# Power_Supply.net
KiCad netlist of a schematic drawn in Altium Designer
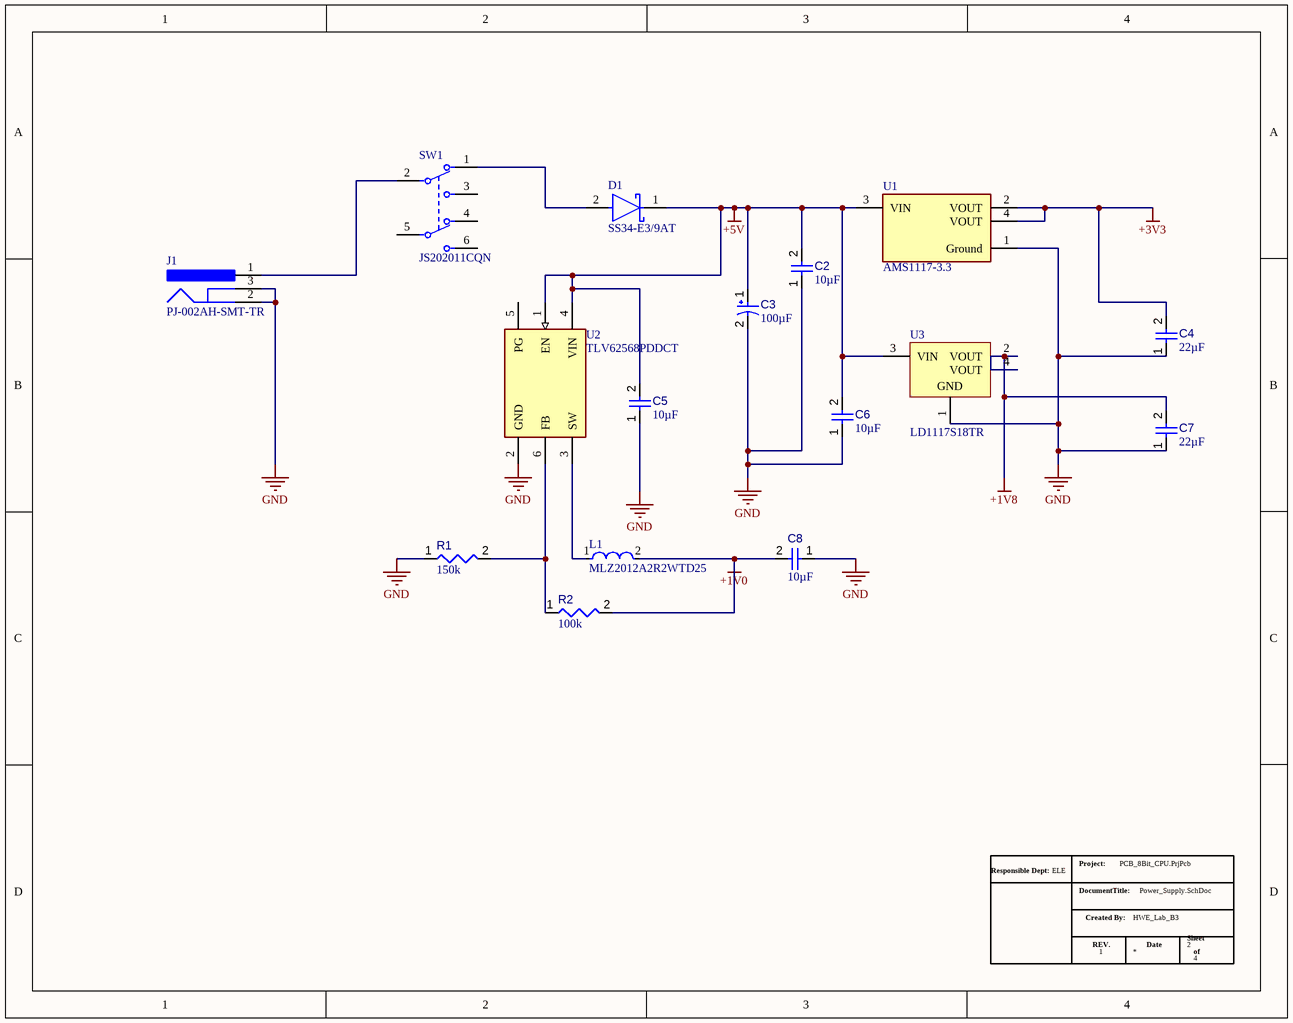
[diagram p0: Power_Supply.SchDoc]

(export (version "E")
  (design (tool "Eeschema 10.0.6"))
  (components
    (comp (ref "C2")
      (value "10µF")
      (footprint "CAPC0805(2012)145_L")
      (description "Chip Capacitor, 10µF +/-20%, 25V, 0805, Thickness 1.45 mm")
      (fields (field (name "TOLERANCE") "10%") (field (name "Comment") "Capacitor 10µF +/-20% 25V 0805"))
      (libsource (lib "MD RUHUL KUDDUS SALEH") (part "CAP-NP-2"))
    )
    (comp (ref "C3")
      (value "100µF")
      (footprint "PNSC-6TPE150MAZB_L")
      (fields (field (name "TOLERANCE") "20%") (field (name "Comment") "Capacitor 6.8µF +/-20% 35V B2"))
      (libsource (lib "MD RUHUL KUDDUS SALEH") (part "CAP-P-2"))
    )
    (comp (ref "C4")
      (value "22µF")
      (footprint "CAPC0805(2012)145_L")
      (description "Chip Capacitor, 10µF +/-20%, 25V, 0805, Thickness 1.45 mm")
      (fields (field (name "TOLERANCE") "10%") (field (name "Comment") "Capacitor 10µF +/-20% 25V 0805"))
      (libsource (lib "MD RUHUL KUDDUS SALEH") (part "CAP-NP-2"))
    )
    (comp (ref "C5")
      (value "10µF")
      (footprint "CAPC0805(2012)145_L")
      (description "Chip Capacitor, 10µF +/-20%, 25V, 0805, Thickness 1.45 mm")
      (fields (field (name "TOLERANCE") "10%") (field (name "Comment") "Capacitor 10µF +/-20% 25V 0805"))
      (libsource (lib "MD RUHUL KUDDUS SALEH") (part "CAP-NP-2"))
    )
    (comp (ref "C6")
      (value "10µF")
      (footprint "CAPC0805(2012)145_L")
      (description "Chip Capacitor, 10µF +/-20%, 25V, 0805, Thickness 1.45 mm")
      (fields (field (name "TOLERANCE") "10%") (field (name "Comment") "Capacitor 10µF +/-20% 25V 0805"))
      (libsource (lib "MD RUHUL KUDDUS SALEH") (part "CAP-NP-2"))
    )
    (comp (ref "C7")
      (value "22µF")
      (footprint "CAPC0805(2012)145_L")
      (description "Chip Capacitor, 10µF +/-20%, 25V, 0805, Thickness 1.45 mm")
      (fields (field (name "TOLERANCE") "10%") (field (name "Comment") "Capacitor 10µF +/-20% 25V 0805"))
      (libsource (lib "MD RUHUL KUDDUS SALEH") (part "CAP-NP-2"))
    )
    (comp (ref "C8")
      (value "10µF")
      (footprint "CAPC0805(2012)145_L")
      (description "Chip Capacitor, 10µF +/-20%, 25V, 0805, Thickness 1.45 mm")
      (fields (field (name "TOLERANCE") "10%") (field (name "Comment") "Capacitor 10µF +/-20% 25V 0805"))
      (libsource (lib "MD RUHUL KUDDUS SALEH") (part "CAP-NP-2"))
    )
    (comp (ref "D1")
      (value "SS34-E3/9AT")
      (footprint "FP-SMC-MFG")
      (description "DIODE SCHOTTKY 40V 3A DO214AB")
      (libsource (lib "Altium Content Vault") (part "c1678fac7984e62e0809fbf79c06691"))
    )
    (comp (ref "J1")
      (value "PJ-002AH-SMT-TR")
      (footprint "CUI-PJ-002AH-4_V")
      (description "DC Power Jack, Right Angle, -25 to 85 degC, 4-Pin 14.8 x 9 x 11 mm SMD, RoHS, Tape and Reel")
      (fields (field (name "MANUFACTURER") "CUIInc.") (field (name "PARTNUMBER") "PJ-002AH"))
      (libsource (lib "Altium Content Vault") (part "JACK-2CD3-RN_B"))
    )
    (comp (ref "L1")
      (value "MLZ2012A2R2WTD25")
      (footprint "FP-MLZ2012-0_85-MFG")
      (description "Shielded Multilayer Inductor 2.2uH ±20% 650mA 195mΩ AEC-Q200 SMD 0805")
      (fields (field (name "TOLERANCE") "20%"))
      (libsource (lib "Altium Content Vault") (part "725321dda6339637d4d059423bc1c3c"))
    )
    (comp (ref "R1")
      (value "150k")
      (footprint "RESC0402(1005)_L")
      (description "Chip Resistor, 100 kOhms, +/-1 %, 63 mW, -55 to 155 degC, 0402")
      (fields (field (name "TOLERANCE") "1%") (field (name "POWER") "63mW"))
      (libsource (lib "MD RUHUL KUDDUS SALEH") (part "RES-2"))
    )
    (comp (ref "R2")
      (value "100k")
      (footprint "RESC0402(1005)_L")
      (description "Chip Resistor, 100 kOhms, +/-1 %, 63 mW, -55 to 155 degC, 0402")
      (fields (field (name "TOLERANCE") "1%") (field (name "POWER") "63mW"))
      (libsource (lib "MD RUHUL KUDDUS SALEH") (part "RES-2"))
    )
    (comp (ref "SW1")
      (value "JS202011CQN")
      (footprint "FP-JS202011CQN-MFG")
      (description "SWITCH SLIDE DPDT 300MA 6V")
      (libsource (lib "Altium Content Vault") (part "a9e2ad50e97b660f430b512a9354c8c"))
    )
    (comp (ref "U1")
      (value "AMS1117-3.3")
      (footprint "FP-AMS1117-IPC_C")
      (description "LDO Voltage Regulators 1A, 3.3V")
      (fields
        (field (name "OCTOPART") "https://octopart.com/ams1117-3.3-advanced+monolithic+systems-25899300")
        (field (name "MANUFACTURER") "Advanced Monolithic Systems")
      )
      (libsource (lib "Altium Content Vault") (part "8bdbb5f8e77002000e30dd2845d0354"))
    )
    (comp (ref "U2")
      (value "TLV62568PDDCT")
      (footprint "FP-DDC0006A-MFG")
      (description "IC REG BUCK ADJ 1A TSOT23-6")
      (libsource (lib "Altium Content Vault") (part "fcfae234c2e21ab116172289ae38564"))
    )
    (comp (ref "U3")
      (value "LD1117S18TR")
      (footprint "SOT-223_M")
      (description "Fixed Low Drop Positive Voltage Regulator, 1.8V, 4-Pin SOT-223, Tape and Reel")
      (libsource (lib "Altium Content Vault") (part "PM-REG-LD1117-SOT4"))
    )
  )
  (nets
    (net (code "1") (name "+1V0") (class "Default")
      (node (ref "C8") (pin "2") (pinfunction "2_2") (pintype "passive"))
      (node (ref "L1") (pin "2") (pinfunction "2_2") (pintype "passive"))
      (node (ref "R2") (pin "2") (pinfunction "2_2") (pintype "passive"))
    )
    (net (code "2") (name "+1V8") (class "Default")
      (node (ref "C7") (pin "2") (pinfunction "2_2") (pintype "passive"))
      (node (ref "U3") (pin "2") (pinfunction "VOUT_2") (pintype "power_in"))
      (node (ref "U3") (pin "4") (pinfunction "VOUT_4") (pintype "power_in"))
    )
    (net (code "3") (name "+3V3") (class "Default")
      (node (ref "C4") (pin "2") (pinfunction "2_2") (pintype "passive"))
      (node (ref "U1") (pin "2") (pinfunction "VOUT_2") (pintype "passive"))
      (node (ref "U1") (pin "4") (pinfunction "VOUT_4") (pintype "passive"))
    )
    (net (code "4") (name "+5V") (class "Default")
      (node (ref "C2") (pin "2") (pinfunction "2_2") (pintype "passive"))
      (node (ref "C3") (pin "1") (pinfunction "1_1") (pintype "passive"))
      (node (ref "C5") (pin "2") (pinfunction "2_2") (pintype "passive"))
      (node (ref "C6") (pin "2") (pinfunction "2_2") (pintype "passive"))
      (node (ref "D1") (pin "1") (pinfunction "C_1") (pintype "passive"))
      (node (ref "U1") (pin "3") (pinfunction "VIN_3") (pintype "power_in"))
      (node (ref "U2") (pin "1") (pinfunction "EN_1") (pintype "input"))
      (node (ref "U2") (pin "4") (pinfunction "VIN_4") (pintype "power_in"))
      (node (ref "U3") (pin "3") (pinfunction "VIN_3") (pintype "power_in"))
    )
    (net (code "5") (name "GND") (class "Default")
      (node (ref "C2") (pin "1") (pinfunction "1_1") (pintype "passive"))
      (node (ref "C3") (pin "2") (pinfunction "2_2") (pintype "passive"))
      (node (ref "C4") (pin "1") (pinfunction "1_1") (pintype "passive"))
      (node (ref "C5") (pin "1") (pinfunction "1_1") (pintype "passive"))
      (node (ref "C6") (pin "1") (pinfunction "1_1") (pintype "passive"))
      (node (ref "C7") (pin "1") (pinfunction "1_1") (pintype "passive"))
      (node (ref "C8") (pin "1") (pinfunction "1_1") (pintype "passive"))
      (node (ref "J1") (pin "2") (pinfunction "2_2") (pintype "passive"))
      (node (ref "J1") (pin "3") (pinfunction "3_3") (pintype "passive"))
      (node (ref "R1") (pin "1") (pinfunction "1_1") (pintype "passive"))
      (node (ref "U1") (pin "1") (pinfunction "Ground_1") (pintype "power_in"))
      (node (ref "U2") (pin "2") (pinfunction "GND_2") (pintype "power_in"))
      (node (ref "U3") (pin "1") (pinfunction "GND_1") (pintype "power_in"))
    )
    (net (code "6") (name "Net-(D1-A)") (class "Default")
      (node (ref "D1") (pin "2") (pinfunction "A_2") (pintype "passive"))
      (node (ref "SW1") (pin "1") (pinfunction "1_1") (pintype "passive"))
    )
    (net (code "7") (name "Net-(J1-Pad1)") (class "Default")
      (node (ref "J1") (pin "1") (pinfunction "1_1") (pintype "passive"))
      (node (ref "SW1") (pin "2") (pinfunction "2_2") (pintype "passive"))
    )
    (net (code "8") (name "Net-(U2-FB)") (class "Default")
      (node (ref "R1") (pin "2") (pinfunction "2_2") (pintype "passive"))
      (node (ref "R2") (pin "1") (pinfunction "1_1") (pintype "passive"))
      (node (ref "U2") (pin "6") (pinfunction "FB_6") (pintype "passive"))
    )
    (net (code "9") (name "Net-(U2-SW)") (class "Default")
      (node (ref "L1") (pin "1") (pinfunction "1_1") (pintype "passive"))
      (node (ref "U2") (pin "3") (pinfunction "SW_3") (pintype "passive"))
    )
    (net (code "10") (name "unconnected-(SW1-Pad3)") (class "Default")
      (node (ref "SW1") (pin "3") (pinfunction "3_3") (pintype "passive"))
    )
    (net (code "11") (name "unconnected-(SW1-Pad4)") (class "Default")
      (node (ref "SW1") (pin "4") (pinfunction "4_4") (pintype "passive"))
    )
    (net (code "12") (name "unconnected-(SW1-Pad5)") (class "Default")
      (node (ref "SW1") (pin "5") (pinfunction "5_5") (pintype "passive"))
    )
    (net (code "13") (name "unconnected-(SW1-Pad6)") (class "Default")
      (node (ref "SW1") (pin "6") (pinfunction "6_6") (pintype "passive"))
    )
    (net (code "14") (name "unconnected-(U2-PG-Pad5)") (class "Default")
      (node (ref "U2") (pin "5") (pinfunction "PG_5") (pintype "open_collector"))
    )
  )
)
